# nfetdriver.net
KiCad netlist of a schematic drawn in EAGLE
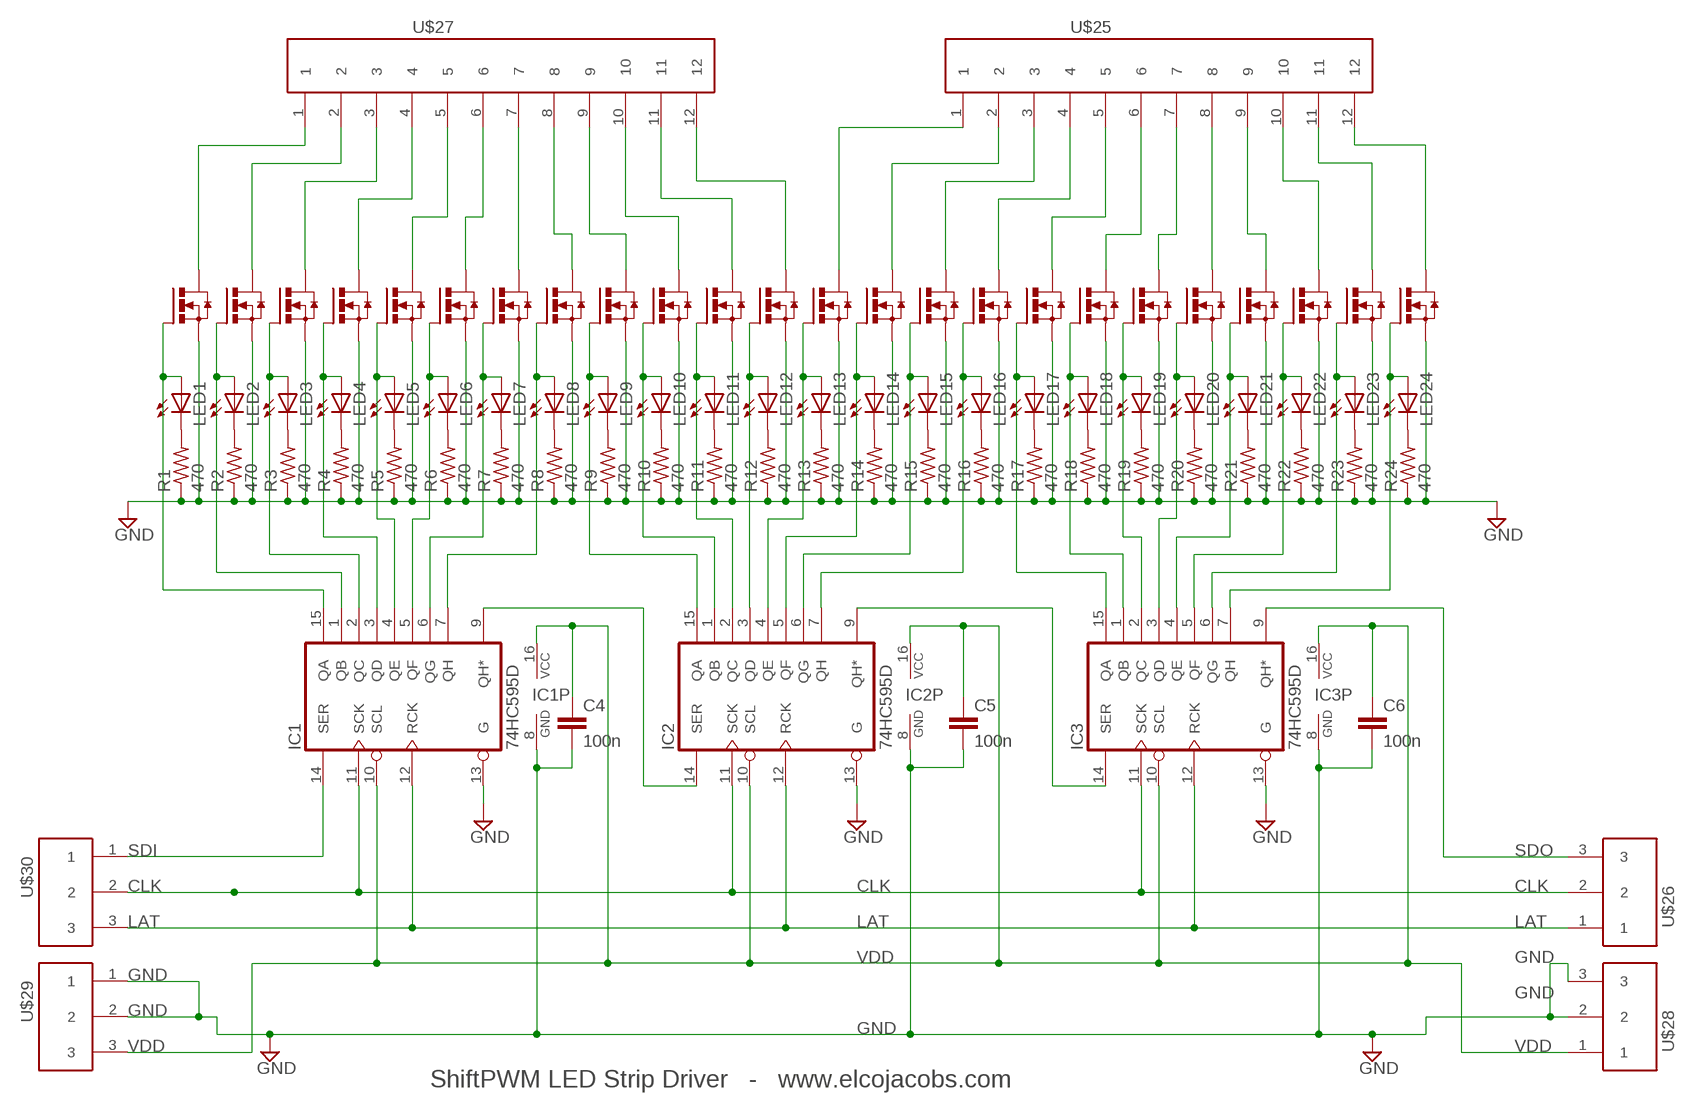
[diagram p0: schematic, sheet 1]

(export (version "E")
  (design (tool "Eeschema 10.0.6"))
  (components
    (comp (ref "C4")
      (value "100n")
      (footprint "eagle-import:C0603")
      (libsource (lib "eagle-import") (part "C-EUC0603"))
    )
    (comp (ref "C5")
      (value "100n")
      (footprint "eagle-import:C0603")
      (libsource (lib "eagle-import") (part "C-EUC0603"))
    )
    (comp (ref "C6")
      (value "100n")
      (footprint "eagle-import:C0603")
      (libsource (lib "eagle-import") (part "C-EUC0603"))
    )
    (comp (ref "IC1")
      (value "74HC595D")
      (footprint "eagle-import:SO16")
      (libsource (lib "eagle-import") (part "74595DHC"))
    )
    (comp (ref "IC2")
      (value "74HC595D")
      (footprint "eagle-import:SO16")
      (libsource (lib "eagle-import") (part "74595DHC"))
    )
    (comp (ref "IC3")
      (value "74HC595D")
      (footprint "eagle-import:SO16")
      (libsource (lib "eagle-import") (part "74595DHC"))
    )
    (comp (ref "LED1")
      (value "LEDCHIPLED_0603")
      (footprint "eagle-import:CHIPLED_0603")
      (libsource (lib "eagle-import") (part "LEDCHIPLED_0603"))
    )
    (comp (ref "LED2")
      (value "LEDCHIPLED_0603")
      (footprint "eagle-import:CHIPLED_0603")
      (libsource (lib "eagle-import") (part "LEDCHIPLED_0603"))
    )
    (comp (ref "LED3")
      (value "LEDCHIPLED_0603")
      (footprint "eagle-import:CHIPLED_0603")
      (libsource (lib "eagle-import") (part "LEDCHIPLED_0603"))
    )
    (comp (ref "LED4")
      (value "LEDCHIPLED_0603")
      (footprint "eagle-import:CHIPLED_0603")
      (libsource (lib "eagle-import") (part "LEDCHIPLED_0603"))
    )
    (comp (ref "LED5")
      (value "LEDCHIPLED_0603")
      (footprint "eagle-import:CHIPLED_0603")
      (libsource (lib "eagle-import") (part "LEDCHIPLED_0603"))
    )
    (comp (ref "LED6")
      (value "LEDCHIPLED_0603")
      (footprint "eagle-import:CHIPLED_0603")
      (libsource (lib "eagle-import") (part "LEDCHIPLED_0603"))
    )
    (comp (ref "LED7")
      (value "LEDCHIPLED_0603")
      (footprint "eagle-import:CHIPLED_0603")
      (libsource (lib "eagle-import") (part "LEDCHIPLED_0603"))
    )
    (comp (ref "LED8")
      (value "LEDCHIPLED_0603")
      (footprint "eagle-import:CHIPLED_0603")
      (libsource (lib "eagle-import") (part "LEDCHIPLED_0603"))
    )
    (comp (ref "LED9")
      (value "LEDCHIPLED_0603")
      (footprint "eagle-import:CHIPLED_0603")
      (libsource (lib "eagle-import") (part "LEDCHIPLED_0603"))
    )
    (comp (ref "LED10")
      (value "LEDCHIPLED_0603")
      (footprint "eagle-import:CHIPLED_0603")
      (libsource (lib "eagle-import") (part "LEDCHIPLED_0603"))
    )
    (comp (ref "LED11")
      (value "LEDCHIPLED_0603")
      (footprint "eagle-import:CHIPLED_0603")
      (libsource (lib "eagle-import") (part "LEDCHIPLED_0603"))
    )
    (comp (ref "LED12")
      (value "LEDCHIPLED_0603")
      (footprint "eagle-import:CHIPLED_0603")
      (libsource (lib "eagle-import") (part "LEDCHIPLED_0603"))
    )
    (comp (ref "LED13")
      (value "LEDCHIPLED_0603")
      (footprint "eagle-import:CHIPLED_0603")
      (libsource (lib "eagle-import") (part "LEDCHIPLED_0603"))
    )
    (comp (ref "LED14")
      (value "LEDCHIPLED_0603")
      (footprint "eagle-import:CHIPLED_0603")
      (libsource (lib "eagle-import") (part "LEDCHIPLED_0603"))
    )
    (comp (ref "LED15")
      (value "LEDCHIPLED_0603")
      (footprint "eagle-import:CHIPLED_0603")
      (libsource (lib "eagle-import") (part "LEDCHIPLED_0603"))
    )
    (comp (ref "LED16")
      (value "LEDCHIPLED_0603")
      (footprint "eagle-import:CHIPLED_0603")
      (libsource (lib "eagle-import") (part "LEDCHIPLED_0603"))
    )
    (comp (ref "LED17")
      (value "LEDCHIPLED_0603")
      (footprint "eagle-import:CHIPLED_0603")
      (libsource (lib "eagle-import") (part "LEDCHIPLED_0603"))
    )
    (comp (ref "LED18")
      (value "LEDCHIPLED_0603")
      (footprint "eagle-import:CHIPLED_0603")
      (libsource (lib "eagle-import") (part "LEDCHIPLED_0603"))
    )
    (comp (ref "LED19")
      (value "LEDCHIPLED_0603")
      (footprint "eagle-import:CHIPLED_0603")
      (libsource (lib "eagle-import") (part "LEDCHIPLED_0603"))
    )
    (comp (ref "LED20")
      (value "LEDCHIPLED_0603")
      (footprint "eagle-import:CHIPLED_0603")
      (libsource (lib "eagle-import") (part "LEDCHIPLED_0603"))
    )
    (comp (ref "LED21")
      (value "LEDCHIPLED_0603")
      (footprint "eagle-import:CHIPLED_0603")
      (libsource (lib "eagle-import") (part "LEDCHIPLED_0603"))
    )
    (comp (ref "LED22")
      (value "LEDCHIPLED_0603")
      (footprint "eagle-import:CHIPLED_0603")
      (libsource (lib "eagle-import") (part "LEDCHIPLED_0603"))
    )
    (comp (ref "LED23")
      (value "LEDCHIPLED_0603")
      (footprint "eagle-import:CHIPLED_0603")
      (libsource (lib "eagle-import") (part "LEDCHIPLED_0603"))
    )
    (comp (ref "LED24")
      (value "LEDCHIPLED_0603")
      (footprint "eagle-import:CHIPLED_0603")
      (libsource (lib "eagle-import") (part "LEDCHIPLED_0603"))
    )
    (comp (ref "R1")
      (value "470")
      (footprint "eagle-import:R0603")
      (libsource (lib "eagle-import") (part "R-US_R0603"))
    )
    (comp (ref "R2")
      (value "470")
      (footprint "eagle-import:R0603")
      (libsource (lib "eagle-import") (part "R-US_R0603"))
    )
    (comp (ref "R3")
      (value "470")
      (footprint "eagle-import:R0603")
      (libsource (lib "eagle-import") (part "R-US_R0603"))
    )
    (comp (ref "R4")
      (value "470")
      (footprint "eagle-import:R0603")
      (libsource (lib "eagle-import") (part "R-US_R0603"))
    )
    (comp (ref "R5")
      (value "470")
      (footprint "eagle-import:R0603")
      (libsource (lib "eagle-import") (part "R-US_R0603"))
    )
    (comp (ref "R6")
      (value "470")
      (footprint "eagle-import:R0603")
      (libsource (lib "eagle-import") (part "R-US_R0603"))
    )
    (comp (ref "R7")
      (value "470")
      (footprint "eagle-import:R0603")
      (libsource (lib "eagle-import") (part "R-US_R0603"))
    )
    (comp (ref "R8")
      (value "470")
      (footprint "eagle-import:R0603")
      (libsource (lib "eagle-import") (part "R-US_R0603"))
    )
    (comp (ref "R9")
      (value "470")
      (footprint "eagle-import:R0603")
      (libsource (lib "eagle-import") (part "R-US_R0603"))
    )
    (comp (ref "R10")
      (value "470")
      (footprint "eagle-import:R0603")
      (libsource (lib "eagle-import") (part "R-US_R0603"))
    )
    (comp (ref "R11")
      (value "470")
      (footprint "eagle-import:R0603")
      (libsource (lib "eagle-import") (part "R-US_R0603"))
    )
    (comp (ref "R12")
      (value "470")
      (footprint "eagle-import:R0603")
      (libsource (lib "eagle-import") (part "R-US_R0603"))
    )
    (comp (ref "R13")
      (value "470")
      (footprint "eagle-import:R0603")
      (libsource (lib "eagle-import") (part "R-US_R0603"))
    )
    (comp (ref "R14")
      (value "470")
      (footprint "eagle-import:R0603")
      (libsource (lib "eagle-import") (part "R-US_R0603"))
    )
    (comp (ref "R15")
      (value "470")
      (footprint "eagle-import:R0603")
      (libsource (lib "eagle-import") (part "R-US_R0603"))
    )
    (comp (ref "R16")
      (value "470")
      (footprint "eagle-import:R0603")
      (libsource (lib "eagle-import") (part "R-US_R0603"))
    )
    (comp (ref "R17")
      (value "470")
      (footprint "eagle-import:R0603")
      (libsource (lib "eagle-import") (part "R-US_R0603"))
    )
    (comp (ref "R18")
      (value "470")
      (footprint "eagle-import:R0603")
      (libsource (lib "eagle-import") (part "R-US_R0603"))
    )
    (comp (ref "R19")
      (value "470")
      (footprint "eagle-import:R0603")
      (libsource (lib "eagle-import") (part "R-US_R0603"))
    )
    (comp (ref "R20")
      (value "470")
      (footprint "eagle-import:R0603")
      (libsource (lib "eagle-import") (part "R-US_R0603"))
    )
    (comp (ref "R21")
      (value "470")
      (footprint "eagle-import:R0603")
      (libsource (lib "eagle-import") (part "R-US_R0603"))
    )
    (comp (ref "R22")
      (value "470")
      (footprint "eagle-import:R0603")
      (libsource (lib "eagle-import") (part "R-US_R0603"))
    )
    (comp (ref "R23")
      (value "470")
      (footprint "eagle-import:R0603")
      (libsource (lib "eagle-import") (part "R-US_R0603"))
    )
    (comp (ref "R24")
      (value "470")
      (footprint "eagle-import:R0603")
      (libsource (lib "eagle-import") (part "R-US_R0603"))
    )
    (comp (ref "U$1")
      (value "SI2302DS")
      (footprint "eagle-import:SOT23")
      (libsource (lib "eagle-import") (part "SI2302DS"))
    )
    (comp (ref "U$2")
      (value "SI2302DS")
      (footprint "eagle-import:SOT23")
      (libsource (lib "eagle-import") (part "SI2302DS"))
    )
    (comp (ref "U$3")
      (value "SI2302DS")
      (footprint "eagle-import:SOT23")
      (libsource (lib "eagle-import") (part "SI2302DS"))
    )
    (comp (ref "U$4")
      (value "SI2302DS")
      (footprint "eagle-import:SOT23")
      (libsource (lib "eagle-import") (part "SI2302DS"))
    )
    (comp (ref "U$5")
      (value "SI2302DS")
      (footprint "eagle-import:SOT23")
      (libsource (lib "eagle-import") (part "SI2302DS"))
    )
    (comp (ref "U$6")
      (value "SI2302DS")
      (footprint "eagle-import:SOT23")
      (libsource (lib "eagle-import") (part "SI2302DS"))
    )
    (comp (ref "U$7")
      (value "SI2302DS")
      (footprint "eagle-import:SOT23")
      (libsource (lib "eagle-import") (part "SI2302DS"))
    )
    (comp (ref "U$8")
      (value "SI2302DS")
      (footprint "eagle-import:SOT23")
      (libsource (lib "eagle-import") (part "SI2302DS"))
    )
    (comp (ref "U$9")
      (value "SI2302DS")
      (footprint "eagle-import:SOT23")
      (libsource (lib "eagle-import") (part "SI2302DS"))
    )
    (comp (ref "U$10")
      (value "SI2302DS")
      (footprint "eagle-import:SOT23")
      (libsource (lib "eagle-import") (part "SI2302DS"))
    )
    (comp (ref "U$11")
      (value "SI2302DS")
      (footprint "eagle-import:SOT23")
      (libsource (lib "eagle-import") (part "SI2302DS"))
    )
    (comp (ref "U$12")
      (value "SI2302DS")
      (footprint "eagle-import:SOT23")
      (libsource (lib "eagle-import") (part "SI2302DS"))
    )
    (comp (ref "U$13")
      (value "SI2302DS")
      (footprint "eagle-import:SOT23")
      (libsource (lib "eagle-import") (part "SI2302DS"))
    )
    (comp (ref "U$14")
      (value "SI2302DS")
      (footprint "eagle-import:SOT23")
      (libsource (lib "eagle-import") (part "SI2302DS"))
    )
    (comp (ref "U$15")
      (value "SI2302DS")
      (footprint "eagle-import:SOT23")
      (libsource (lib "eagle-import") (part "SI2302DS"))
    )
    (comp (ref "U$16")
      (value "SI2302DS")
      (footprint "eagle-import:SOT23")
      (libsource (lib "eagle-import") (part "SI2302DS"))
    )
    (comp (ref "U$17")
      (value "SI2302DS")
      (footprint "eagle-import:SOT23")
      (libsource (lib "eagle-import") (part "SI2302DS"))
    )
    (comp (ref "U$18")
      (value "SI2302DS")
      (footprint "eagle-import:SOT23")
      (libsource (lib "eagle-import") (part "SI2302DS"))
    )
    (comp (ref "U$19")
      (value "SI2302DS")
      (footprint "eagle-import:SOT23")
      (libsource (lib "eagle-import") (part "SI2302DS"))
    )
    (comp (ref "U$20")
      (value "SI2302DS")
      (footprint "eagle-import:SOT23")
      (libsource (lib "eagle-import") (part "SI2302DS"))
    )
    (comp (ref "U$21")
      (value "SI2302DS")
      (footprint "eagle-import:SOT23")
      (libsource (lib "eagle-import") (part "SI2302DS"))
    )
    (comp (ref "U$22")
      (value "SI2302DS")
      (footprint "eagle-import:SOT23")
      (libsource (lib "eagle-import") (part "SI2302DS"))
    )
    (comp (ref "U$23")
      (value "SI2302DS")
      (footprint "eagle-import:SOT23")
      (libsource (lib "eagle-import") (part "SI2302DS"))
    )
    (comp (ref "U$24")
      (value "SI2302DS")
      (footprint "eagle-import:SOT23")
      (libsource (lib "eagle-import") (part "SI2302DS"))
    )
    (comp (ref "U$25")
      (value "3.5MM12P")
      (footprint "eagle-import:3.5MM12P")
      (libsource (lib "eagle-import") (part "3.5MM12P"))
    )
    (comp (ref "U$26")
      (value "3.5MM3PHORIZONTAL")
      (footprint "eagle-import:3.5MM3P")
      (libsource (lib "eagle-import") (part "3.5MM3PHORIZONTAL"))
    )
    (comp (ref "U$27")
      (value "3.5MM12P")
      (footprint "eagle-import:3.5MM12P")
      (libsource (lib "eagle-import") (part "3.5MM12P"))
    )
    (comp (ref "U$28")
      (value "3.5MM3PHORIZONTAL")
      (footprint "eagle-import:3.5MM3P")
      (libsource (lib "eagle-import") (part "3.5MM3PHORIZONTAL"))
    )
    (comp (ref "U$29")
      (value "3.5MM3PHORIZONTAL")
      (footprint "eagle-import:3.5MM3P")
      (libsource (lib "eagle-import") (part "3.5MM3PHORIZONTAL"))
    )
    (comp (ref "U$30")
      (value "3.5MM3PHORIZONTAL")
      (footprint "eagle-import:3.5MM3P")
      (libsource (lib "eagle-import") (part "3.5MM3PHORIZONTAL"))
    )
  )
  (nets
    (net (code "1") (name "/CLK") (class "Default")
      (node (ref "IC1") (pin "11") (pinfunction "SCK_11") (pintype "input"))
      (node (ref "IC2") (pin "11") (pinfunction "SCK_11") (pintype "input"))
      (node (ref "IC3") (pin "11") (pinfunction "SCK_11") (pintype "input"))
      (node (ref "U$26") (pin "2") (pinfunction "2_2") (pintype "bidirectional"))
      (node (ref "U$30") (pin "2") (pinfunction "2_2") (pintype "bidirectional"))
    )
    (net (code "2") (name "/LAT") (class "Default")
      (node (ref "IC1") (pin "12") (pinfunction "RCK_12") (pintype "input"))
      (node (ref "IC2") (pin "12") (pinfunction "RCK_12") (pintype "input"))
      (node (ref "IC3") (pin "12") (pinfunction "RCK_12") (pintype "input"))
      (node (ref "U$26") (pin "1") (pinfunction "1_1") (pintype "bidirectional"))
      (node (ref "U$30") (pin "3") (pinfunction "3_3") (pintype "bidirectional"))
    )
    (net (code "3") (name "/VDD") (class "Default")
      (node (ref "C4") (pin "1") (pinfunction "1_1") (pintype "passive"))
      (node (ref "C5") (pin "1") (pinfunction "1_1") (pintype "passive"))
      (node (ref "C6") (pin "1") (pinfunction "1_1") (pintype "passive"))
      (node (ref "IC1") (pin "10") (pinfunction "SCL_10") (pintype "input"))
      (node (ref "IC1") (pin "16") (pinfunction "VCC_16") (pintype "power_in"))
      (node (ref "IC2") (pin "10") (pinfunction "SCL_10") (pintype "input"))
      (node (ref "IC2") (pin "16") (pinfunction "VCC_16") (pintype "power_in"))
      (node (ref "IC3") (pin "10") (pinfunction "SCL_10") (pintype "input"))
      (node (ref "IC3") (pin "16") (pinfunction "VCC_16") (pintype "power_in"))
      (node (ref "U$28") (pin "1") (pinfunction "1_1") (pintype "bidirectional"))
      (node (ref "U$29") (pin "3") (pinfunction "3_3") (pintype "bidirectional"))
    )
    (net (code "4") (name "GND") (class "Default")
      (node (ref "C4") (pin "2") (pinfunction "2_2") (pintype "passive"))
      (node (ref "C5") (pin "2") (pinfunction "2_2") (pintype "passive"))
      (node (ref "C6") (pin "2") (pinfunction "2_2") (pintype "passive"))
      (node (ref "IC1") (pin "13") (pinfunction "G_13") (pintype "input"))
      (node (ref "IC1") (pin "8") (pinfunction "GND_8") (pintype "power_in"))
      (node (ref "IC2") (pin "13") (pinfunction "G_13") (pintype "input"))
      (node (ref "IC2") (pin "8") (pinfunction "GND_8") (pintype "power_in"))
      (node (ref "IC3") (pin "13") (pinfunction "G_13") (pintype "input"))
      (node (ref "IC3") (pin "8") (pinfunction "GND_8") (pintype "power_in"))
      (node (ref "R1") (pin "1") (pinfunction "1_1") (pintype "passive"))
      (node (ref "R10") (pin "1") (pinfunction "1_1") (pintype "passive"))
      (node (ref "R11") (pin "1") (pinfunction "1_1") (pintype "passive"))
      (node (ref "R12") (pin "1") (pinfunction "1_1") (pintype "passive"))
      (node (ref "R13") (pin "1") (pinfunction "1_1") (pintype "passive"))
      (node (ref "R14") (pin "1") (pinfunction "1_1") (pintype "passive"))
      (node (ref "R15") (pin "1") (pinfunction "1_1") (pintype "passive"))
      (node (ref "R16") (pin "1") (pinfunction "1_1") (pintype "passive"))
      (node (ref "R17") (pin "1") (pinfunction "1_1") (pintype "passive"))
      (node (ref "R18") (pin "1") (pinfunction "1_1") (pintype "passive"))
      (node (ref "R19") (pin "1") (pinfunction "1_1") (pintype "passive"))
      (node (ref "R2") (pin "1") (pinfunction "1_1") (pintype "passive"))
      (node (ref "R20") (pin "1") (pinfunction "1_1") (pintype "passive"))
      (node (ref "R21") (pin "1") (pinfunction "1_1") (pintype "passive"))
      (node (ref "R22") (pin "1") (pinfunction "1_1") (pintype "passive"))
      (node (ref "R23") (pin "1") (pinfunction "1_1") (pintype "passive"))
      (node (ref "R24") (pin "1") (pinfunction "1_1") (pintype "passive"))
      (node (ref "R3") (pin "1") (pinfunction "1_1") (pintype "passive"))
      (node (ref "R4") (pin "1") (pinfunction "1_1") (pintype "passive"))
      (node (ref "R5") (pin "1") (pinfunction "1_1") (pintype "passive"))
      (node (ref "R6") (pin "1") (pinfunction "1_1") (pintype "passive"))
      (node (ref "R7") (pin "1") (pinfunction "1_1") (pintype "passive"))
      (node (ref "R8") (pin "1") (pinfunction "1_1") (pintype "passive"))
      (node (ref "R9") (pin "1") (pinfunction "1_1") (pintype "passive"))
      (node (ref "U$1") (pin "SOURCE") (pinfunction "S_SOURCE") (pintype "passive"))
      (node (ref "U$10") (pin "SOURCE") (pinfunction "S_SOURCE") (pintype "passive"))
      (node (ref "U$11") (pin "SOURCE") (pinfunction "S_SOURCE") (pintype "passive"))
      (node (ref "U$12") (pin "SOURCE") (pinfunction "S_SOURCE") (pintype "passive"))
      (node (ref "U$13") (pin "SOURCE") (pinfunction "S_SOURCE") (pintype "passive"))
      (node (ref "U$14") (pin "SOURCE") (pinfunction "S_SOURCE") (pintype "passive"))
      (node (ref "U$15") (pin "SOURCE") (pinfunction "S_SOURCE") (pintype "passive"))
      (node (ref "U$16") (pin "SOURCE") (pinfunction "S_SOURCE") (pintype "passive"))
      (node (ref "U$17") (pin "SOURCE") (pinfunction "S_SOURCE") (pintype "passive"))
      (node (ref "U$18") (pin "SOURCE") (pinfunction "S_SOURCE") (pintype "passive"))
      (node (ref "U$19") (pin "SOURCE") (pinfunction "S_SOURCE") (pintype "passive"))
      (node (ref "U$2") (pin "SOURCE") (pinfunction "S_SOURCE") (pintype "passive"))
      (node (ref "U$20") (pin "SOURCE") (pinfunction "S_SOURCE") (pintype "passive"))
      (node (ref "U$21") (pin "SOURCE") (pinfunction "S_SOURCE") (pintype "passive"))
      (node (ref "U$22") (pin "SOURCE") (pinfunction "S_SOURCE") (pintype "passive"))
      (node (ref "U$23") (pin "SOURCE") (pinfunction "S_SOURCE") (pintype "passive"))
      (node (ref "U$24") (pin "SOURCE") (pinfunction "S_SOURCE") (pintype "passive"))
      (node (ref "U$28") (pin "2") (pinfunction "2_2") (pintype "bidirectional"))
      (node (ref "U$28") (pin "3") (pinfunction "3_3") (pintype "bidirectional"))
      (node (ref "U$29") (pin "1") (pinfunction "1_1") (pintype "bidirectional"))
      (node (ref "U$29") (pin "2") (pinfunction "2_2") (pintype "bidirectional"))
      (node (ref "U$3") (pin "SOURCE") (pinfunction "S_SOURCE") (pintype "passive"))
      (node (ref "U$4") (pin "SOURCE") (pinfunction "S_SOURCE") (pintype "passive"))
      (node (ref "U$5") (pin "SOURCE") (pinfunction "S_SOURCE") (pintype "passive"))
      (node (ref "U$6") (pin "SOURCE") (pinfunction "S_SOURCE") (pintype "passive"))
      (node (ref "U$7") (pin "SOURCE") (pinfunction "S_SOURCE") (pintype "passive"))
      (node (ref "U$8") (pin "SOURCE") (pinfunction "S_SOURCE") (pintype "passive"))
      (node (ref "U$9") (pin "SOURCE") (pinfunction "S_SOURCE") (pintype "passive"))
    )
    (net (code "5") (name "Net-(IC1A-QA)") (class "Default")
      (node (ref "IC1") (pin "15") (pinfunction "QA_15") (pintype "tri_state"))
      (node (ref "LED1") (pin "A") (pinfunction "A_A") (pintype "passive"))
      (node (ref "U$1") (pin "GATE") (pinfunction "G_GATE") (pintype "passive"))
    )
    (net (code "6") (name "Net-(IC1A-QB)") (class "Default")
      (node (ref "IC1") (pin "1") (pinfunction "QB_1") (pintype "tri_state"))
      (node (ref "LED2") (pin "A") (pinfunction "A_A") (pintype "passive"))
      (node (ref "U$2") (pin "GATE") (pinfunction "G_GATE") (pintype "passive"))
    )
    (net (code "7") (name "Net-(IC1A-QC)") (class "Default")
      (node (ref "IC1") (pin "2") (pinfunction "QC_2") (pintype "tri_state"))
      (node (ref "LED3") (pin "A") (pinfunction "A_A") (pintype "passive"))
      (node (ref "U$3") (pin "GATE") (pinfunction "G_GATE") (pintype "passive"))
    )
    (net (code "8") (name "Net-(IC1A-QD)") (class "Default")
      (node (ref "IC1") (pin "3") (pinfunction "QD_3") (pintype "tri_state"))
      (node (ref "LED4") (pin "A") (pinfunction "A_A") (pintype "passive"))
      (node (ref "U$4") (pin "GATE") (pinfunction "G_GATE") (pintype "passive"))
    )
    (net (code "9") (name "Net-(IC1A-QE)") (class "Default")
      (node (ref "IC1") (pin "4") (pinfunction "QE_4") (pintype "tri_state"))
      (node (ref "LED5") (pin "A") (pinfunction "A_A") (pintype "passive"))
      (node (ref "U$5") (pin "GATE") (pinfunction "G_GATE") (pintype "passive"))
    )
    (net (code "10") (name "Net-(IC1A-QF)") (class "Default")
      (node (ref "IC1") (pin "5") (pinfunction "QF_5") (pintype "tri_state"))
      (node (ref "LED6") (pin "A") (pinfunction "A_A") (pintype "passive"))
      (node (ref "U$6") (pin "GATE") (pinfunction "G_GATE") (pintype "passive"))
    )
    (net (code "11") (name "Net-(IC1A-QG)") (class "Default")
      (node (ref "IC1") (pin "6") (pinfunction "QG_6") (pintype "tri_state"))
      (node (ref "LED7") (pin "A") (pinfunction "A_A") (pintype "passive"))
      (node (ref "U$7") (pin "GATE") (pinfunction "G_GATE") (pintype "passive"))
    )
    (net (code "12") (name "Net-(IC1A-QH)") (class "Default")
      (node (ref "IC1") (pin "7") (pinfunction "QH_7") (pintype "tri_state"))
      (node (ref "LED8") (pin "A") (pinfunction "A_A") (pintype "passive"))
      (node (ref "U$8") (pin "GATE") (pinfunction "G_GATE") (pintype "passive"))
    )
    (net (code "13") (name "Net-(IC1A-QH*)") (class "Default")
      (node (ref "IC1") (pin "9") (pinfunction "QH*_9") (pintype "tri_state"))
      (node (ref "IC2") (pin "14") (pinfunction "SER_14") (pintype "input"))
    )
    (net (code "14") (name "Net-(IC1A-SER)") (class "Default")
      (node (ref "IC1") (pin "14") (pinfunction "SER_14") (pintype "input"))
      (node (ref "U$30") (pin "1") (pinfunction "1_1") (pintype "bidirectional"))
    )
    (net (code "15") (name "Net-(IC2A-QA)") (class "Default")
      (node (ref "IC2") (pin "15") (pinfunction "QA_15") (pintype "tri_state"))
      (node (ref "LED9") (pin "A") (pinfunction "A_A") (pintype "passive"))
      (node (ref "U$9") (pin "GATE") (pinfunction "G_GATE") (pintype "passive"))
    )
    (net (code "16") (name "Net-(IC2A-QB)") (class "Default")
      (node (ref "IC2") (pin "1") (pinfunction "QB_1") (pintype "tri_state"))
      (node (ref "LED10") (pin "A") (pinfunction "A_A") (pintype "passive"))
      (node (ref "U$10") (pin "GATE") (pinfunction "G_GATE") (pintype "passive"))
    )
    (net (code "17") (name "Net-(IC2A-QC)") (class "Default")
      (node (ref "IC2") (pin "2") (pinfunction "QC_2") (pintype "tri_state"))
      (node (ref "LED11") (pin "A") (pinfunction "A_A") (pintype "passive"))
      (node (ref "U$11") (pin "GATE") (pinfunction "G_GATE") (pintype "passive"))
    )
    (net (code "18") (name "Net-(IC2A-QD)") (class "Default")
      (node (ref "IC2") (pin "3") (pinfunction "QD_3") (pintype "tri_state"))
      (node (ref "LED12") (pin "A") (pinfunction "A_A") (pintype "passive"))
      (node (ref "U$12") (pin "GATE") (pinfunction "G_GATE") (pintype "passive"))
    )
    (net (code "19") (name "Net-(IC2A-QE)") (class "Default")
      (node (ref "IC2") (pin "4") (pinfunction "QE_4") (pintype "tri_state"))
      (node (ref "LED13") (pin "A") (pinfunction "A_A") (pintype "passive"))
      (node (ref "U$13") (pin "GATE") (pinfunction "G_GATE") (pintype "passive"))
    )
    (net (code "20") (name "Net-(IC2A-QF)") (class "Default")
      (node (ref "IC2") (pin "5") (pinfunction "QF_5") (pintype "tri_state"))
      (node (ref "LED14") (pin "A") (pinfunction "A_A") (pintype "passive"))
      (node (ref "U$14") (pin "GATE") (pinfunction "G_GATE") (pintype "passive"))
    )
    (net (code "21") (name "Net-(IC2A-QG)") (class "Default")
      (node (ref "IC2") (pin "6") (pinfunction "QG_6") (pintype "tri_state"))
      (node (ref "LED15") (pin "A") (pinfunction "A_A") (pintype "passive"))
      (node (ref "U$15") (pin "GATE") (pinfunction "G_GATE") (pintype "passive"))
    )
    (net (code "22") (name "Net-(IC2A-QH)") (class "Default")
      (node (ref "IC2") (pin "7") (pinfunction "QH_7") (pintype "tri_state"))
      (node (ref "LED16") (pin "A") (pinfunction "A_A") (pintype "passive"))
      (node (ref "U$16") (pin "GATE") (pinfunction "G_GATE") (pintype "passive"))
    )
    (net (code "23") (name "Net-(IC2A-QH*)") (class "Default")
      (node (ref "IC2") (pin "9") (pinfunction "QH*_9") (pintype "tri_state"))
      (node (ref "IC3") (pin "14") (pinfunction "SER_14") (pintype "input"))
    )
    (net (code "24") (name "Net-(IC3A-QA)") (class "Default")
      (node (ref "IC3") (pin "15") (pinfunction "QA_15") (pintype "tri_state"))
      (node (ref "LED17") (pin "A") (pinfunction "A_A") (pintype "passive"))
      (node (ref "U$17") (pin "GATE") (pinfunction "G_GATE") (pintype "passive"))
    )
    (net (code "25") (name "Net-(IC3A-QB)") (class "Default")
      (node (ref "IC3") (pin "1") (pinfunction "QB_1") (pintype "tri_state"))
      (node (ref "LED18") (pin "A") (pinfunction "A_A") (pintype "passive"))
      (node (ref "U$18") (pin "GATE") (pinfunction "G_GATE") (pintype "passive"))
    )
    (net (code "26") (name "Net-(IC3A-QC)") (class "Default")
      (node (ref "IC3") (pin "2") (pinfunction "QC_2") (pintype "tri_state"))
      (node (ref "LED19") (pin "A") (pinfunction "A_A") (pintype "passive"))
      (node (ref "U$19") (pin "GATE") (pinfunction "G_GATE") (pintype "passive"))
    )
    (net (code "27") (name "Net-(IC3A-QD)") (class "Default")
      (node (ref "IC3") (pin "3") (pinfunction "QD_3") (pintype "tri_state"))
      (node (ref "LED20") (pin "A") (pinfunction "A_A") (pintype "passive"))
      (node (ref "U$20") (pin "GATE") (pinfunction "G_GATE") (pintype "passive"))
    )
    (net (code "28") (name "Net-(IC3A-QE)") (class "Default")
      (node (ref "IC3") (pin "4") (pinfunction "QE_4") (pintype "tri_state"))
      (node (ref "LED21") (pin "A") (pinfunction "A_A") (pintype "passive"))
      (node (ref "U$21") (pin "GATE") (pinfunction "G_GATE") (pintype "passive"))
    )
    (net (code "29") (name "Net-(IC3A-QF)") (class "Default")
      (node (ref "IC3") (pin "5") (pinfunction "QF_5") (pintype "tri_state"))
      (node (ref "LED22") (pin "A") (pinfunction "A_A") (pintype "passive"))
      (node (ref "U$22") (pin "GATE") (pinfunction "G_GATE") (pintype "passive"))
    )
    (net (code "30") (name "Net-(IC3A-QG)") (class "Default")
      (node (ref "IC3") (pin "6") (pinfunction "QG_6") (pintype "tri_state"))
      (node (ref "LED23") (pin "A") (pinfunction "A_A") (pintype "passive"))
      (node (ref "U$23") (pin "GATE") (pinfunction "G_GATE") (pintype "passive"))
    )
    (net (code "31") (name "Net-(IC3A-QH)") (class "Default")
      (node (ref "IC3") (pin "7") (pinfunction "QH_7") (pintype "tri_state"))
      (node (ref "LED24") (pin "A") (pinfunction "A_A") (pintype "passive"))
      (node (ref "U$24") (pin "GATE") (pinfunction "G_GATE") (pintype "passive"))
    )
    (net (code "32") (name "Net-(IC3A-QH*)") (class "Default")
      (node (ref "IC3") (pin "9") (pinfunction "QH*_9") (pintype "tri_state"))
      (node (ref "U$26") (pin "3") (pinfunction "3_3") (pintype "bidirectional"))
    )
    (net (code "33") (name "Net-(LED1-PadC)") (class "Default")
      (node (ref "LED1") (pin "C") (pinfunction "C_C") (pintype "passive"))
      (node (ref "R1") (pin "2") (pinfunction "2_2") (pintype "passive"))
    )
    (net (code "34") (name "Net-(LED2-PadC)") (class "Default")
      (node (ref "LED2") (pin "C") (pinfunction "C_C") (pintype "passive"))
      (node (ref "R2") (pin "2") (pinfunction "2_2") (pintype "passive"))
    )
    (net (code "35") (name "Net-(LED3-PadC)") (class "Default")
      (node (ref "LED3") (pin "C") (pinfunction "C_C") (pintype "passive"))
      (node (ref "R3") (pin "2") (pinfunction "2_2") (pintype "passive"))
    )
    (net (code "36") (name "Net-(LED4-PadC)") (class "Default")
      (node (ref "LED4") (pin "C") (pinfunction "C_C") (pintype "passive"))
      (node (ref "R4") (pin "2") (pinfunction "2_2") (pintype "passive"))
    )
    (net (code "37") (name "Net-(LED5-PadC)") (class "Default")
      (node (ref "LED5") (pin "C") (pinfunction "C_C") (pintype "passive"))
      (node (ref "R5") (pin "2") (pinfunction "2_2") (pintype "passive"))
    )
    (net (code "38") (name "Net-(LED6-PadC)") (class "Default")
      (node (ref "LED6") (pin "C") (pinfunction "C_C") (pintype "passive"))
      (node (ref "R6") (pin "2") (pinfunction "2_2") (pintype "passive"))
    )
    (net (code "39") (name "Net-(LED7-PadC)") (class "Default")
      (node (ref "LED7") (pin "C") (pinfunction "C_C") (pintype "passive"))
      (node (ref "R7") (pin "2") (pinfunction "2_2") (pintype "passive"))
    )
    (net (code "40") (name "Net-(LED8-PadC)") (class "Default")
      (node (ref "LED8") (pin "C") (pinfunction "C_C") (pintype "passive"))
      (node (ref "R8") (pin "2") (pinfunction "2_2") (pintype "passive"))
    )
    (net (code "41") (name "Net-(LED9-PadC)") (class "Default")
      (node (ref "LED9") (pin "C") (pinfunction "C_C") (pintype "passive"))
      (node (ref "R9") (pin "2") (pinfunction "2_2") (pintype "passive"))
    )
    (net (code "42") (name "Net-(LED10-PadC)") (class "Default")
      (node (ref "LED10") (pin "C") (pinfunction "C_C") (pintype "passive"))
      (node (ref "R10") (pin "2") (pinfunction "2_2") (pintype "passive"))
    )
    (net (code "43") (name "Net-(LED11-PadC)") (class "Default")
      (node (ref "LED11") (pin "C") (pinfunction "C_C") (pintype "passive"))
      (node (ref "R11") (pin "2") (pinfunction "2_2") (pintype "passive"))
    )
    (net (code "44") (name "Net-(LED12-PadC)") (class "Default")
      (node (ref "LED12") (pin "C") (pinfunction "C_C") (pintype "passive"))
      (node (ref "R12") (pin "2") (pinfunction "2_2") (pintype "passive"))
    )
    (net (code "45") (name "Net-(LED13-PadC)") (class "Default")
      (node (ref "LED13") (pin "C") (pinfunction "C_C") (pintype "passive"))
      (node (ref "R13") (pin "2") (pinfunction "2_2") (pintype "passive"))
    )
    (net (code "46") (name "Net-(LED14-PadC)") (class "Default")
      (node (ref "LED14") (pin "C") (pinfunction "C_C") (pintype "passive"))
      (node (ref "R14") (pin "2") (pinfunction "2_2") (pintype "passive"))
    )
    (net (code "47") (name "Net-(LED15-PadC)") (class "Default")
      (node (ref "LED15") (pin "C") (pinfunction "C_C") (pintype "passive"))
      (node (ref "R15") (pin "2") (pinfunction "2_2") (pintype "passive"))
    )
    (net (code "48") (name "Net-(LED16-PadC)") (class "Default")
      (node (ref "LED16") (pin "C") (pinfunction "C_C") (pintype "passive"))
      (node (ref "R16") (pin "2") (pinfunction "2_2") (pintype "passive"))
    )
    (net (code "49") (name "Net-(LED17-PadC)") (class "Default")
      (node (ref "LED17") (pin "C") (pinfunction "C_C") (pintype "passive"))
      (node (ref "R17") (pin "2") (pinfunction "2_2") (pintype "passive"))
    )
    (net (code "50") (name "Net-(LED18-PadC)") (class "Default")
      (node (ref "LED18") (pin "C") (pinfunction "C_C") (pintype "passive"))
      (node (ref "R18") (pin "2") (pinfunction "2_2") (pintype "passive"))
    )
    (net (code "51") (name "Net-(LED19-PadC)") (class "Default")
      (node (ref "LED19") (pin "C") (pinfunction "C_C") (pintype "passive"))
      (node (ref "R19") (pin "2") (pinfunction "2_2") (pintype "passive"))
    )
    (net (code "52") (name "Net-(LED20-PadC)") (class "Default")
      (node (ref "LED20") (pin "C") (pinfunction "C_C") (pintype "passive"))
      (node (ref "R20") (pin "2") (pinfunction "2_2") (pintype "passive"))
    )
    (net (code "53") (name "Net-(LED21-PadC)") (class "Default")
      (node (ref "LED21") (pin "C") (pinfunction "C_C") (pintype "passive"))
      (node (ref "R21") (pin "2") (pinfunction "2_2") (pintype "passive"))
    )
    (net (code "54") (name "Net-(LED22-PadC)") (class "Default")
      (node (ref "LED22") (pin "C") (pinfunction "C_C") (pintype "passive"))
      (node (ref "R22") (pin "2") (pinfunction "2_2") (pintype "passive"))
    )
    (net (code "55") (name "Net-(LED23-PadC)") (class "Default")
      (node (ref "LED23") (pin "C") (pinfunction "C_C") (pintype "passive"))
      (node (ref "R23") (pin "2") (pinfunction "2_2") (pintype "passive"))
    )
    (net (code "56") (name "Net-(LED24-PadC)") (class "Default")
      (node (ref "LED24") (pin "C") (pinfunction "C_C") (pintype "passive"))
      (node (ref "R24") (pin "2") (pinfunction "2_2") (pintype "passive"))
    )
    (net (code "57") (name "Net-(U$1-D)") (class "Default")
      (node (ref "U$1") (pin "DRAIN") (pinfunction "D_DRAIN") (pintype "passive"))
      (node (ref "U$27") (pin "1") (pinfunction "1_1") (pintype "bidirectional"))
    )
    (net (code "58") (name "Net-(U$2-D)") (class "Default")
      (node (ref "U$2") (pin "DRAIN") (pinfunction "D_DRAIN") (pintype "passive"))
      (node (ref "U$27") (pin "2") (pinfunction "2_2") (pintype "bidirectional"))
    )
    (net (code "59") (name "Net-(U$3-D)") (class "Default")
      (node (ref "U$27") (pin "3") (pinfunction "3_3") (pintype "bidirectional"))
      (node (ref "U$3") (pin "DRAIN") (pinfunction "D_DRAIN") (pintype "passive"))
    )
    (net (code "60") (name "Net-(U$4-D)") (class "Default")
      (node (ref "U$27") (pin "4") (pinfunction "4_4") (pintype "bidirectional"))
      (node (ref "U$4") (pin "DRAIN") (pinfunction "D_DRAIN") (pintype "passive"))
    )
    (net (code "61") (name "Net-(U$5-D)") (class "Default")
      (node (ref "U$27") (pin "5") (pinfunction "5_5") (pintype "bidirectional"))
      (node (ref "U$5") (pin "DRAIN") (pinfunction "D_DRAIN") (pintype "passive"))
    )
    (net (code "62") (name "Net-(U$6-D)") (class "Default")
      (node (ref "U$27") (pin "6") (pinfunction "6_6") (pintype "bidirectional"))
      (node (ref "U$6") (pin "DRAIN") (pinfunction "D_DRAIN") (pintype "passive"))
    )
    (net (code "63") (name "Net-(U$7-D)") (class "Default")
      (node (ref "U$27") (pin "7") (pinfunction "7_7") (pintype "bidirectional"))
      (node (ref "U$7") (pin "DRAIN") (pinfunction "D_DRAIN") (pintype "passive"))
    )
    (net (code "64") (name "Net-(U$8-D)") (class "Default")
      (node (ref "U$27") (pin "8") (pinfunction "8_8") (pintype "bidirectional"))
      (node (ref "U$8") (pin "DRAIN") (pinfunction "D_DRAIN") (pintype "passive"))
    )
    (net (code "65") (name "Net-(U$9-D)") (class "Default")
      (node (ref "U$27") (pin "9") (pinfunction "9_9") (pintype "bidirectional"))
      (node (ref "U$9") (pin "DRAIN") (pinfunction "D_DRAIN") (pintype "passive"))
    )
    (net (code "66") (name "Net-(U$10-D)") (class "Default")
      (node (ref "U$10") (pin "DRAIN") (pinfunction "D_DRAIN") (pintype "passive"))
      (node (ref "U$27") (pin "10") (pinfunction "10_10") (pintype "bidirectional"))
    )
    (net (code "67") (name "Net-(U$11-D)") (class "Default")
      (node (ref "U$11") (pin "DRAIN") (pinfunction "D_DRAIN") (pintype "passive"))
      (node (ref "U$27") (pin "11") (pinfunction "11_11") (pintype "bidirectional"))
    )
    (net (code "68") (name "Net-(U$12-D)") (class "Default")
      (node (ref "U$12") (pin "DRAIN") (pinfunction "D_DRAIN") (pintype "passive"))
      (node (ref "U$27") (pin "12") (pinfunction "12_12") (pintype "bidirectional"))
    )
    (net (code "69") (name "Net-(U$13-D)") (class "Default")
      (node (ref "U$13") (pin "DRAIN") (pinfunction "D_DRAIN") (pintype "passive"))
      (node (ref "U$25") (pin "1") (pinfunction "1_1") (pintype "bidirectional"))
    )
    (net (code "70") (name "Net-(U$14-D)") (class "Default")
      (node (ref "U$14") (pin "DRAIN") (pinfunction "D_DRAIN") (pintype "passive"))
      (node (ref "U$25") (pin "2") (pinfunction "2_2") (pintype "bidirectional"))
    )
    (net (code "71") (name "Net-(U$15-D)") (class "Default")
      (node (ref "U$15") (pin "DRAIN") (pinfunction "D_DRAIN") (pintype "passive"))
      (node (ref "U$25") (pin "3") (pinfunction "3_3") (pintype "bidirectional"))
    )
    (net (code "72") (name "Net-(U$16-D)") (class "Default")
      (node (ref "U$16") (pin "DRAIN") (pinfunction "D_DRAIN") (pintype "passive"))
      (node (ref "U$25") (pin "4") (pinfunction "4_4") (pintype "bidirectional"))
    )
    (net (code "73") (name "Net-(U$17-D)") (class "Default")
      (node (ref "U$17") (pin "DRAIN") (pinfunction "D_DRAIN") (pintype "passive"))
      (node (ref "U$25") (pin "5") (pinfunction "5_5") (pintype "bidirectional"))
    )
    (net (code "74") (name "Net-(U$18-D)") (class "Default")
      (node (ref "U$18") (pin "DRAIN") (pinfunction "D_DRAIN") (pintype "passive"))
      (node (ref "U$25") (pin "6") (pinfunction "6_6") (pintype "bidirectional"))
    )
    (net (code "75") (name "Net-(U$19-D)") (class "Default")
      (node (ref "U$19") (pin "DRAIN") (pinfunction "D_DRAIN") (pintype "passive"))
      (node (ref "U$25") (pin "7") (pinfunction "7_7") (pintype "bidirectional"))
    )
    (net (code "76") (name "Net-(U$20-D)") (class "Default")
      (node (ref "U$20") (pin "DRAIN") (pinfunction "D_DRAIN") (pintype "passive"))
      (node (ref "U$25") (pin "8") (pinfunction "8_8") (pintype "bidirectional"))
    )
    (net (code "77") (name "Net-(U$21-D)") (class "Default")
      (node (ref "U$21") (pin "DRAIN") (pinfunction "D_DRAIN") (pintype "passive"))
      (node (ref "U$25") (pin "9") (pinfunction "9_9") (pintype "bidirectional"))
    )
    (net (code "78") (name "Net-(U$22-D)") (class "Default")
      (node (ref "U$22") (pin "DRAIN") (pinfunction "D_DRAIN") (pintype "passive"))
      (node (ref "U$25") (pin "10") (pinfunction "10_10") (pintype "bidirectional"))
    )
    (net (code "79") (name "Net-(U$23-D)") (class "Default")
      (node (ref "U$23") (pin "DRAIN") (pinfunction "D_DRAIN") (pintype "passive"))
      (node (ref "U$25") (pin "11") (pinfunction "11_11") (pintype "bidirectional"))
    )
    (net (code "80") (name "Net-(U$24-D)") (class "Default")
      (node (ref "U$24") (pin "DRAIN") (pinfunction "D_DRAIN") (pintype "passive"))
      (node (ref "U$25") (pin "12") (pinfunction "12_12") (pintype "bidirectional"))
    )
  )
)
